# FluxR3-v2.net
KiCad netlist of a schematic drawn in EAGLE
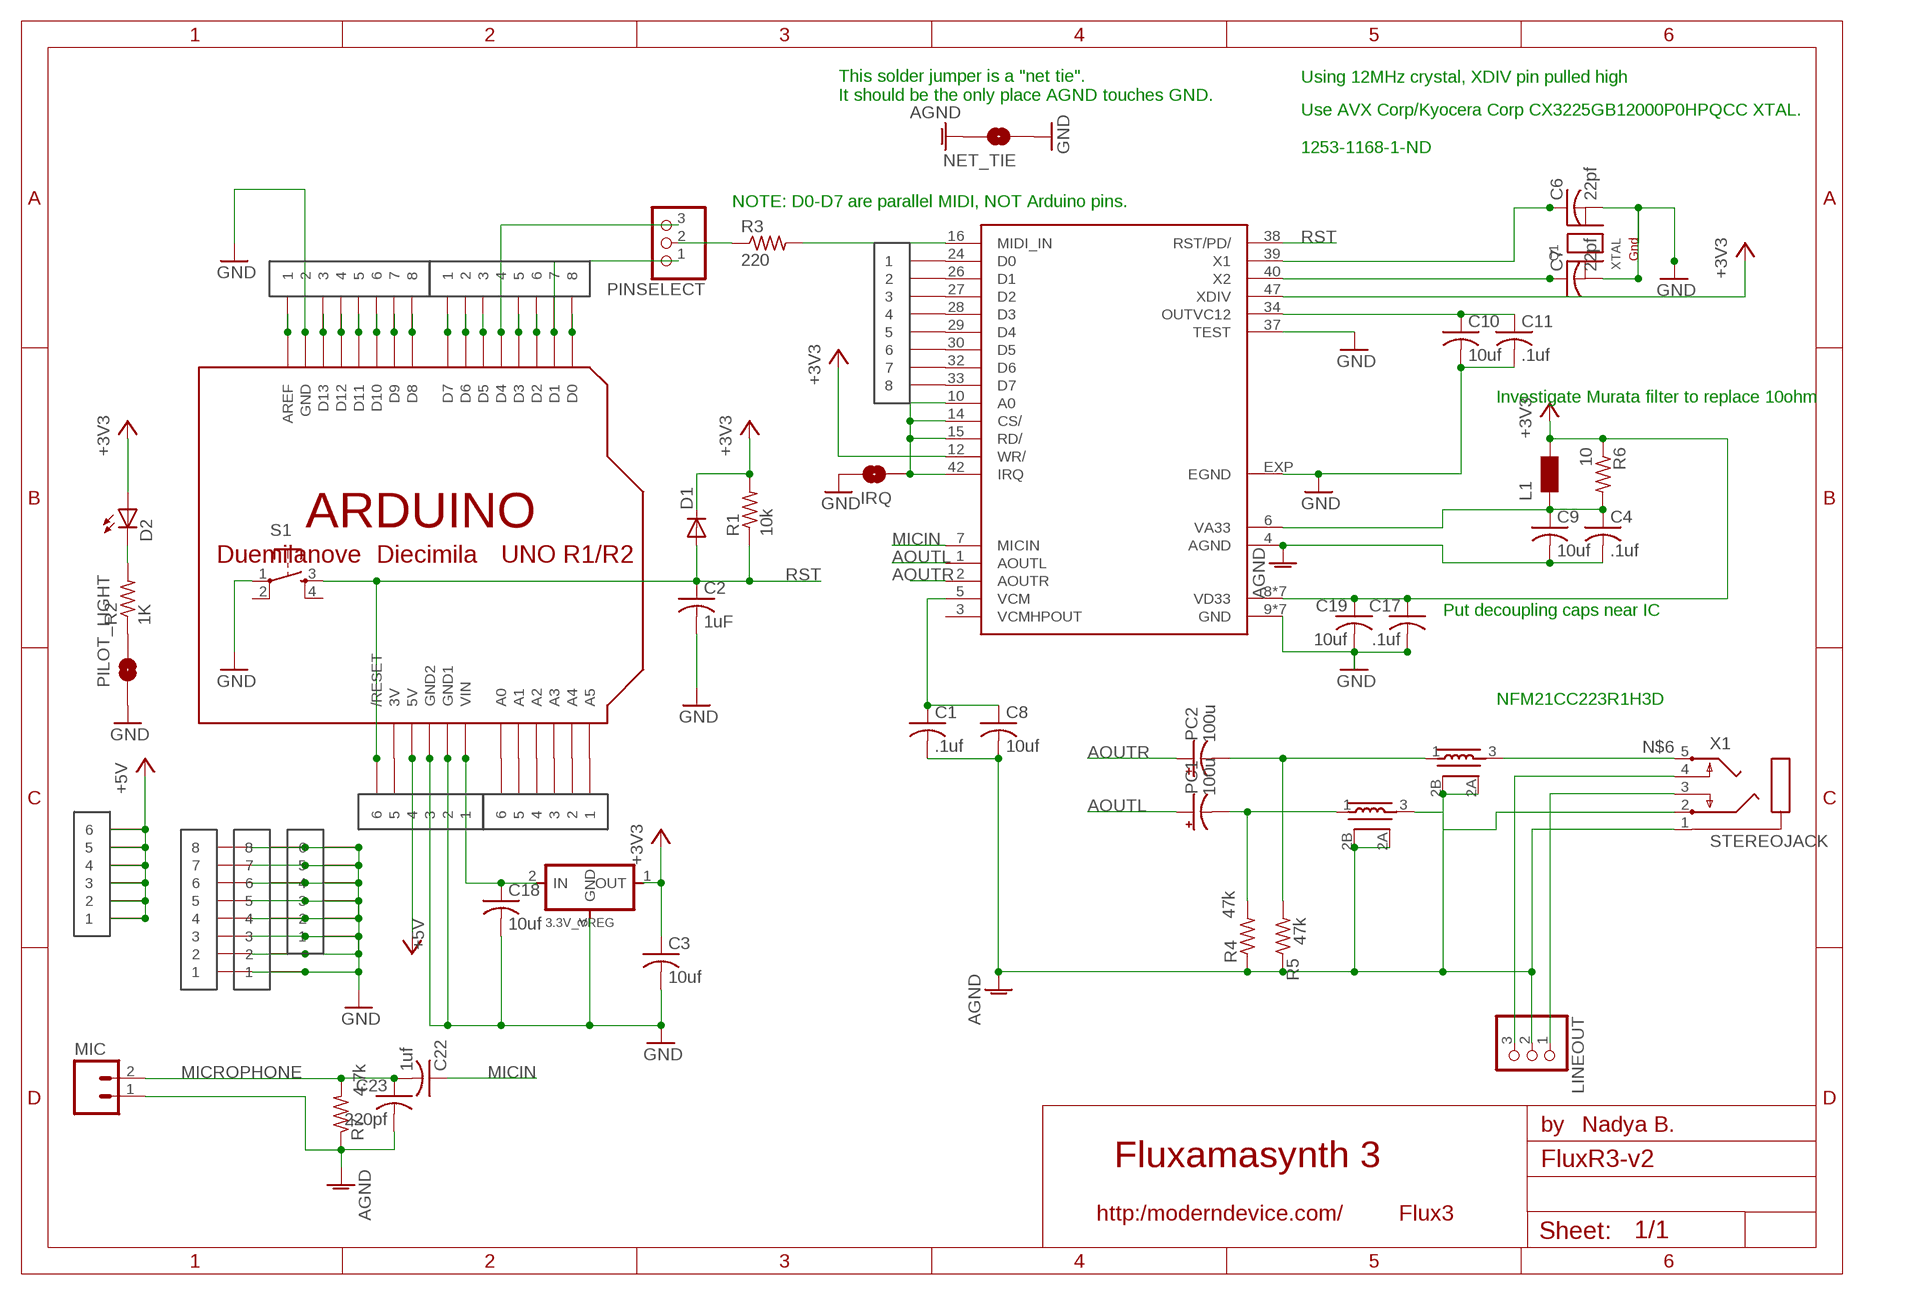
[diagram p0: schematic, sheet 1]

(export (version "E")
  (design (tool "Eeschema 10.0.6"))
  (components
    (comp (ref "3.3V_VREG")
      (value "REGULATORSOT23")
      (footprint "eagle-import:SOT23")
      (libsource (lib "eagle-import") (part "REGULATORSOT23"))
    )
    (comp (ref "ARDUINO")
      (value "ARDUINO-NOHOLE")
      (footprint "eagle-import:ARDUINO-NOHOLE")
      (libsource (lib "eagle-import") (part "ARDUINO-NOHOLE"))
    )
    (comp (ref "C1")
      (value ".1uf")
      (footprint "eagle-import:C0603K")
      (libsource (lib "eagle-import") (part "C-USC0603K"))
    )
    (comp (ref "C2")
      (value "1uF")
      (footprint "eagle-import:C0805")
      (libsource (lib "eagle-import") (part "C-USC0805"))
    )
    (comp (ref "C3")
      (value "10uf")
      (footprint "eagle-import:C0805")
      (libsource (lib "eagle-import") (part "C-USC0805"))
    )
    (comp (ref "C4")
      (value ".1uf")
      (footprint "eagle-import:C0603K")
      (libsource (lib "eagle-import") (part "C-USC0603K"))
    )
    (comp (ref "C6")
      (value "22pf")
      (footprint "eagle-import:C0805")
      (libsource (lib "eagle-import") (part "C-USC0805"))
    )
    (comp (ref "C7")
      (value "22pf")
      (footprint "eagle-import:C0805")
      (libsource (lib "eagle-import") (part "C-USC0805"))
    )
    (comp (ref "C8")
      (value "10uf")
      (footprint "eagle-import:C0805")
      (libsource (lib "eagle-import") (part "C-USC0805"))
    )
    (comp (ref "C9")
      (value "10uf")
      (footprint "eagle-import:C0805")
      (libsource (lib "eagle-import") (part "C-USC0805"))
    )
    (comp (ref "C10")
      (value "10uf")
      (footprint "eagle-import:C0805")
      (libsource (lib "eagle-import") (part "C-USC0805"))
    )
    (comp (ref "C11")
      (value ".1uf")
      (footprint "eagle-import:C0603K")
      (libsource (lib "eagle-import") (part "C-USC0603K"))
    )
    (comp (ref "C17")
      (value ".1uf")
      (footprint "eagle-import:C0603K")
      (libsource (lib "eagle-import") (part "C-USC0603K"))
    )
    (comp (ref "C18")
      (value "10uf")
      (footprint "eagle-import:C0805")
      (libsource (lib "eagle-import") (part "C-USC0805"))
    )
    (comp (ref "C19")
      (value "10uf")
      (footprint "eagle-import:C0805")
      (libsource (lib "eagle-import") (part "C-USC0805"))
    )
    (comp (ref "C22")
      (value "1uf")
      (footprint "eagle-import:C0805")
      (libsource (lib "eagle-import") (part "C-USC0805"))
    )
    (comp (ref "C23")
      (value "220pf")
      (footprint "eagle-import:C0805")
      (libsource (lib "eagle-import") (part "C-USC0805"))
    )
    (comp (ref "D1")
      (value "DIODESOD123")
      (footprint "eagle-import:SOD123")
      (libsource (lib "eagle-import") (part "DIODESOD123"))
    )
    (comp (ref "D2")
      (value "LED1206")
      (footprint "eagle-import:LED-1206")
      (libsource (lib "eagle-import") (part "LED1206"))
    )
    (comp (ref "IRQ")
      (value "MODERNDEVICE_SOLDERJUMPERTRACE")
      (footprint "eagle-import:MODERNDEVICE_SJ_2S-TRACE")
      (libsource (lib "eagle-import") (part "MODERNDEVICE_SOLDERJUMPERTRACE"))
    )
    (comp (ref "L1")
      (value "FERRITE_BEAD_L0603")
      (footprint "eagle-import:R0603")
      (libsource (lib "eagle-import") (part "FERRITE_BEAD_L0603"))
    )
    (comp (ref "LINEOUT")
      (value "PINHD-1X3")
      (footprint "eagle-import:1X03")
      (libsource (lib "eagle-import") (part "PINHD-1X3"))
    )
    (comp (ref "MIC")
      (value "M02PTH")
      (footprint "eagle-import:1X02")
      (libsource (lib "eagle-import") (part "M02PTH"))
    )
    (comp (ref "MIDI")
      (value "1X8_CLEAN")
      (footprint "eagle-import:1X8_CLEAN")
      (libsource (lib "eagle-import") (part "1X8_CLEAN"))
    )
    (comp (ref "NET_TIE")
      (value "MODERNDEVICE_SOLDERJUMPERTRACE")
      (footprint "eagle-import:MODERNDEVICE_SJ_2S-TRACE")
      (libsource (lib "eagle-import") (part "MODERNDEVICE_SOLDERJUMPERTRACE"))
    )
    (comp (ref "PC1")
      (value "100u")
      (footprint "eagle-import:PANASONIC_E")
      (libsource (lib "eagle-import") (part "CPOL-USE"))
    )
    (comp (ref "PC2")
      (value "100u")
      (footprint "eagle-import:PANASONIC_E")
      (libsource (lib "eagle-import") (part "CPOL-USE"))
    )
    (comp (ref "PILOT_LIGHT")
      (value "MODERNDEVICE_SOLDERJUMPERTRACE")
      (footprint "eagle-import:MODERNDEVICE_SJ_2S-TRACE")
      (libsource (lib "eagle-import") (part "MODERNDEVICE_SOLDERJUMPERTRACE"))
    )
    (comp (ref "PINSELECT")
      (value "PINHD-1X3")
      (footprint "eagle-import:1X03")
      (libsource (lib "eagle-import") (part "PINHD-1X3"))
    )
    (comp (ref "Q1")
      (value "XTAL")
      (footprint "eagle-import:MODERNDEVICE_NX3225")
      (libsource (lib "eagle-import") (part "MODERNDEVICE_XTAL-4-3225"))
    )
    (comp (ref "R1")
      (value "10k")
      (footprint "eagle-import:M0805")
      (libsource (lib "eagle-import") (part "R-US_M0805"))
    )
    (comp (ref "R2")
      (value "1K")
      (footprint "eagle-import:M0805")
      (libsource (lib "eagle-import") (part "R-US_M0805"))
    )
    (comp (ref "R3")
      (value "220")
      (footprint "eagle-import:M0805")
      (libsource (lib "eagle-import") (part "R-US_M0805"))
    )
    (comp (ref "R4")
      (value "47k")
      (footprint "eagle-import:R0603")
      (libsource (lib "eagle-import") (part "R-US_R0603"))
    )
    (comp (ref "R5")
      (value "47k")
      (footprint "eagle-import:R0603")
      (libsource (lib "eagle-import") (part "R-US_R0603"))
    )
    (comp (ref "R6")
      (value "10")
      (footprint "eagle-import:M0805")
      (libsource (lib "eagle-import") (part "R-US_M0805"))
    )
    (comp (ref "R7")
      (value "4.7k")
      (footprint "eagle-import:M0805")
      (libsource (lib "eagle-import") (part "R-US_M0805"))
    )
    (comp (ref "S1")
      (value "6MM_SWITCH6MM_SWITCH")
      (footprint "eagle-import:6MM_SWITCH")
      (libsource (lib "eagle-import") (part "6MM_SWITCH6MM_SWITCH"))
    )
    (comp (ref "SAM2695")
      (value "SAM2695")
      (footprint "eagle-import:QFN48")
      (libsource (lib "eagle-import") (part "SAM2695"))
    )
    (comp (ref "U$1")
      (value "1X8_CLEAN")
      (footprint "eagle-import:1X8_CLEAN")
      (libsource (lib "eagle-import") (part "1X8_CLEAN"))
    )
    (comp (ref "U$2")
      (value "1X6_CLEAN")
      (footprint "eagle-import:1X6_CLEAN")
      (libsource (lib "eagle-import") (part "1X6_CLEAN"))
    )
    (comp (ref "U$3")
      (value "1X6_CLEAN")
      (footprint "eagle-import:1X6_CLEAN")
      (libsource (lib "eagle-import") (part "1X6_CLEAN"))
    )
    (comp (ref "U$4")
      (value "NFM21CC223R1H3D")
      (footprint "eagle-import:3PC")
      (libsource (lib "eagle-import") (part "NFM21CC223R1H3D"))
    )
    (comp (ref "U$5")
      (value "NFM21CC223R1H3D")
      (footprint "eagle-import:3PC")
      (libsource (lib "eagle-import") (part "NFM21CC223R1H3D"))
    )
    (comp (ref "U$6")
      (value "1X6_CLEAN")
      (footprint "eagle-import:1X6_CLEAN")
      (libsource (lib "eagle-import") (part "1X6_CLEAN"))
    )
    (comp (ref "U$8")
      (value "1X6_CLEAN")
      (footprint "eagle-import:1X6_CLEAN")
      (libsource (lib "eagle-import") (part "1X6_CLEAN"))
    )
    (comp (ref "U$9")
      (value "1X8_CLEAN")
      (footprint "eagle-import:1X8_CLEAN")
      (libsource (lib "eagle-import") (part "1X8_CLEAN"))
    )
    (comp (ref "U$11")
      (value "1X8_CLEAN")
      (footprint "eagle-import:1X8_CLEAN")
      (libsource (lib "eagle-import") (part "1X8_CLEAN"))
    )
    (comp (ref "U$13")
      (value "1X8_CLEAN")
      (footprint "eagle-import:1X8_CLEAN")
      (libsource (lib "eagle-import") (part "1X8_CLEAN"))
    )
    (comp (ref "X1")
      (value "STEREOJACK")
      (footprint "eagle-import:STX3100")
      (libsource (lib "eagle-import") (part "STEREOJACK"))
    )
  )
  (nets
    (net (code "1") (name "+3V3") (class "Default")
      (node (ref "3.3V_VREG") (pin "1") (pinfunction "OUT_1") (pintype "bidirectional"))
      (node (ref "C17") (pin "1") (pinfunction "1_1") (pintype "passive"))
      (node (ref "C19") (pin "1") (pinfunction "1_1") (pintype "passive"))
      (node (ref "C3") (pin "1") (pinfunction "1_1") (pintype "passive"))
      (node (ref "D1") (pin "CATHODE") (pinfunction "C_CATHODE") (pintype "passive"))
      (node (ref "D2") (pin "A") (pinfunction "A_A") (pintype "passive"))
      (node (ref "L1") (pin "2") (pinfunction "2_2") (pintype "passive"))
      (node (ref "R1") (pin "2") (pinfunction "2_2") (pintype "passive"))
      (node (ref "R6") (pin "1") (pinfunction "1_1") (pintype "passive"))
      (node (ref "SAM2695") (pin "11") (pinfunction "VD33_11") (pintype "power_in"))
      (node (ref "SAM2695") (pin "12") (pinfunction "WR/_12") (pintype "input"))
      (node (ref "SAM2695") (pin "20") (pinfunction "VD33_20") (pintype "power_in"))
      (node (ref "SAM2695") (pin "31") (pinfunction "VD33_31") (pintype "power_in"))
      (node (ref "SAM2695") (pin "35") (pinfunction "VD33_35") (pintype "power_in"))
      (node (ref "SAM2695") (pin "41") (pinfunction "VD33_41") (pintype "power_in"))
      (node (ref "SAM2695") (pin "46") (pinfunction "VD33_46") (pintype "power_in"))
      (node (ref "SAM2695") (pin "47") (pinfunction "XDIV_47") (pintype "input"))
      (node (ref "SAM2695") (pin "8") (pinfunction "VD33_8") (pintype "power_in"))
    )
    (net (code "2") (name "+5V") (class "Default")
      (node (ref "ARDUINO") (pin "5V") (pinfunction "5V_5V") (pintype "power_in"))
      (node (ref "U$2") (pin "P$1") (pinfunction "1_P$1") (pintype "bidirectional"))
      (node (ref "U$2") (pin "P$2") (pinfunction "2_P$2") (pintype "bidirectional"))
      (node (ref "U$2") (pin "P$3") (pinfunction "3_P$3") (pintype "bidirectional"))
      (node (ref "U$2") (pin "P$4") (pinfunction "4_P$4") (pintype "bidirectional"))
      (node (ref "U$2") (pin "P$5") (pinfunction "5_P$5") (pintype "bidirectional"))
      (node (ref "U$2") (pin "P$6") (pinfunction "6_P$6") (pintype "bidirectional"))
      (node (ref "U$6") (pin "P$4") (pinfunction "4_P$4") (pintype "bidirectional"))
    )
    (net (code "3") (name "/AOUTL") (class "Default")
      (node (ref "PC1") (pin "+") (pinfunction "+_+") (pintype "passive"))
      (node (ref "SAM2695") (pin "1") (pinfunction "AOUTL_1") (pintype "output"))
    )
    (net (code "4") (name "/AOUTR") (class "Default")
      (node (ref "PC2") (pin "+") (pinfunction "+_+") (pintype "passive"))
      (node (ref "SAM2695") (pin "2") (pinfunction "AOUTR_2") (pintype "output"))
    )
    (net (code "5") (name "/MICIN") (class "Default")
      (node (ref "C22") (pin "1") (pinfunction "1_1") (pintype "passive"))
      (node (ref "SAM2695") (pin "7") (pinfunction "MICIN_7") (pintype "input"))
    )
    (net (code "6") (name "/MICROPHONE") (class "Default")
      (node (ref "C22") (pin "2") (pinfunction "2_2") (pintype "passive"))
      (node (ref "C23") (pin "1") (pinfunction "1_1") (pintype "passive"))
      (node (ref "MIC") (pin "2") (pinfunction "2_2") (pintype "passive"))
      (node (ref "R7") (pin "2") (pinfunction "2_2") (pintype "passive"))
    )
    (net (code "7") (name "/N$6") (class "Default")
      (node (ref "U$4") (pin "3") (pinfunction "3_3") (pintype "bidirectional"))
      (node (ref "X1") (pin "5") (pinfunction "5_5") (pintype "passive"))
    )
    (net (code "8") (name "/RST") (class "Default")
      (node (ref "ARDUINO") (pin "RESET") (pinfunction "/RESET_RESET") (pintype "bidirectional"))
      (node (ref "C2") (pin "1") (pinfunction "1_1") (pintype "passive"))
      (node (ref "D1") (pin "ANODE") (pinfunction "A_ANODE") (pintype "passive"))
      (node (ref "R1") (pin "1") (pinfunction "1_1") (pintype "passive"))
      (node (ref "S1") (pin "3") (pinfunction "S_3") (pintype "passive"))
      (node (ref "SAM2695") (pin "38") (pinfunction "RST/PD/_38") (pintype "input"))
      (node (ref "U$6") (pin "P$6") (pinfunction "6_P$6") (pintype "bidirectional"))
    )
    (net (code "9") (name "AGND") (class "Default")
      (node (ref "C1") (pin "2") (pinfunction "2_2") (pintype "passive"))
      (node (ref "C23") (pin "2") (pinfunction "2_2") (pintype "passive"))
      (node (ref "C4") (pin "2") (pinfunction "2_2") (pintype "passive"))
      (node (ref "C8") (pin "2") (pinfunction "2_2") (pintype "passive"))
      (node (ref "C9") (pin "2") (pinfunction "2_2") (pintype "passive"))
      (node (ref "LINEOUT") (pin "2") (pinfunction "2_2") (pintype "passive"))
      (node (ref "MIC") (pin "1") (pinfunction "1_1") (pintype "passive"))
      (node (ref "NET_TIE") (pin "2") (pinfunction "2_2") (pintype "passive"))
      (node (ref "R4") (pin "1") (pinfunction "1_1") (pintype "passive"))
      (node (ref "R5") (pin "1") (pinfunction "1_1") (pintype "passive"))
      (node (ref "R7") (pin "1") (pinfunction "1_1") (pintype "passive"))
      (node (ref "SAM2695") (pin "4") (pinfunction "AGND_4") (pintype "power_in"))
      (node (ref "U$4") (pin "2A") (pinfunction "2A_2A") (pintype "power_in"))
      (node (ref "U$4") (pin "2B") (pinfunction "2B_2B") (pintype "power_in"))
      (node (ref "U$5") (pin "2A") (pinfunction "2A_2A") (pintype "power_in"))
      (node (ref "U$5") (pin "2B") (pinfunction "2B_2B") (pintype "power_in"))
      (node (ref "X1") (pin "1") (pinfunction "1_1") (pintype "passive"))
    )
    (net (code "10") (name "GND") (class "Default")
      (node (ref "3.3V_VREG") (pin "3") (pinfunction "GND_3") (pintype "bidirectional"))
      (node (ref "ARDUINO") (pin "GND") (pinfunction "GND_GND") (pintype "power_in"))
      (node (ref "ARDUINO") (pin "GND1") (pinfunction "GND1_GND1") (pintype "power_in"))
      (node (ref "ARDUINO") (pin "GND2") (pinfunction "GND2_GND2") (pintype "power_in"))
      (node (ref "C10") (pin "2") (pinfunction "2_2") (pintype "passive"))
      (node (ref "C11") (pin "2") (pinfunction "2_2") (pintype "passive"))
      (node (ref "C17") (pin "2") (pinfunction "2_2") (pintype "passive"))
      (node (ref "C18") (pin "2") (pinfunction "2_2") (pintype "passive"))
      (node (ref "C19") (pin "2") (pinfunction "2_2") (pintype "passive"))
      (node (ref "C2") (pin "2") (pinfunction "2_2") (pintype "passive"))
      (node (ref "C3") (pin "2") (pinfunction "2_2") (pintype "passive"))
      (node (ref "C6") (pin "2") (pinfunction "2_2") (pintype "passive"))
      (node (ref "C7") (pin "2") (pinfunction "2_2") (pintype "passive"))
      (node (ref "IRQ") (pin "2") (pinfunction "2_2") (pintype "passive"))
      (node (ref "NET_TIE") (pin "1") (pinfunction "1_1") (pintype "passive"))
      (node (ref "PILOT_LIGHT") (pin "1") (pinfunction "1_1") (pintype "passive"))
      (node (ref "Q1") (pin "2") (pinfunction "G2_2") (pintype "power_in"))
      (node (ref "Q1") (pin "4") (pinfunction "G1_4") (pintype "power_in"))
      (node (ref "S1") (pin "1") (pinfunction "P_1") (pintype "passive"))
      (node (ref "SAM2695") (pin "13") (pinfunction "GND_13") (pintype "power_in"))
      (node (ref "SAM2695") (pin "18") (pinfunction "GND_18") (pintype "power_in"))
      (node (ref "SAM2695") (pin "25") (pinfunction "GND_25") (pintype "power_in"))
      (node (ref "SAM2695") (pin "36") (pinfunction "GND_36") (pintype "power_in"))
      (node (ref "SAM2695") (pin "37") (pinfunction "TEST_37") (pintype "input"))
      (node (ref "SAM2695") (pin "45") (pinfunction "GND_45") (pintype "power_in"))
      (node (ref "SAM2695") (pin "48") (pinfunction "GND_48") (pintype "power_in"))
      (node (ref "SAM2695") (pin "9") (pinfunction "GND_9") (pintype "power_in"))
      (node (ref "SAM2695") (pin "EXP") (pinfunction "EGND_EXP") (pintype "power_in"))
      (node (ref "U$1") (pin "P$1") (pinfunction "1_P$1") (pintype "bidirectional"))
      (node (ref "U$1") (pin "P$2") (pinfunction "2_P$2") (pintype "bidirectional"))
      (node (ref "U$1") (pin "P$3") (pinfunction "3_P$3") (pintype "bidirectional"))
      (node (ref "U$1") (pin "P$4") (pinfunction "4_P$4") (pintype "bidirectional"))
      (node (ref "U$1") (pin "P$5") (pinfunction "5_P$5") (pintype "bidirectional"))
      (node (ref "U$1") (pin "P$6") (pinfunction "6_P$6") (pintype "bidirectional"))
      (node (ref "U$1") (pin "P$7") (pinfunction "7_P$7") (pintype "bidirectional"))
      (node (ref "U$1") (pin "P$8") (pinfunction "8_P$8") (pintype "bidirectional"))
      (node (ref "U$11") (pin "P$1") (pinfunction "1_P$1") (pintype "bidirectional"))
      (node (ref "U$11") (pin "P$2") (pinfunction "2_P$2") (pintype "bidirectional"))
      (node (ref "U$11") (pin "P$3") (pinfunction "3_P$3") (pintype "bidirectional"))
      (node (ref "U$11") (pin "P$4") (pinfunction "4_P$4") (pintype "bidirectional"))
      (node (ref "U$11") (pin "P$5") (pinfunction "5_P$5") (pintype "bidirectional"))
      (node (ref "U$11") (pin "P$6") (pinfunction "6_P$6") (pintype "bidirectional"))
      (node (ref "U$11") (pin "P$7") (pinfunction "7_P$7") (pintype "bidirectional"))
      (node (ref "U$11") (pin "P$8") (pinfunction "8_P$8") (pintype "bidirectional"))
      (node (ref "U$13") (pin "P$2") (pinfunction "2_P$2") (pintype "bidirectional"))
      (node (ref "U$3") (pin "P$1") (pinfunction "1_P$1") (pintype "bidirectional"))
      (node (ref "U$3") (pin "P$2") (pinfunction "2_P$2") (pintype "bidirectional"))
      (node (ref "U$3") (pin "P$3") (pinfunction "3_P$3") (pintype "bidirectional"))
      (node (ref "U$3") (pin "P$4") (pinfunction "4_P$4") (pintype "bidirectional"))
      (node (ref "U$3") (pin "P$5") (pinfunction "5_P$5") (pintype "bidirectional"))
      (node (ref "U$3") (pin "P$6") (pinfunction "6_P$6") (pintype "bidirectional"))
      (node (ref "U$6") (pin "P$2") (pinfunction "2_P$2") (pintype "bidirectional"))
      (node (ref "U$6") (pin "P$3") (pinfunction "3_P$3") (pintype "bidirectional"))
    )
    (net (code "11") (name "Net-(3.3V_VREG-IN)") (class "Default")
      (node (ref "3.3V_VREG") (pin "2") (pinfunction "IN_2") (pintype "bidirectional"))
      (node (ref "ARDUINO") (pin "VIN") (pinfunction "VIN_VIN") (pintype "power_in"))
      (node (ref "C18") (pin "1") (pinfunction "1_1") (pintype "passive"))
      (node (ref "U$6") (pin "P$1") (pinfunction "1_P$1") (pintype "bidirectional"))
    )
    (net (code "12") (name "Net-(D2-PadC)") (class "Default")
      (node (ref "D2") (pin "C") (pinfunction "C_C") (pintype "passive"))
      (node (ref "R2") (pin "2") (pinfunction "2_2") (pintype "passive"))
    )
    (net (code "13") (name "Net-(LINEOUT-Pad1)") (class "Default")
      (node (ref "LINEOUT") (pin "1") (pinfunction "1_1") (pintype "passive"))
      (node (ref "X1") (pin "3") (pinfunction "3_3") (pintype "passive"))
    )
    (net (code "14") (name "Net-(LINEOUT-Pad3)") (class "Default")
      (node (ref "LINEOUT") (pin "3") (pinfunction "3_3") (pintype "passive"))
      (node (ref "X1") (pin "4") (pinfunction "4_4") (pintype "passive"))
    )
    (net (code "15") (name "Net-(MIDI-1)") (class "Default")
      (node (ref "MIDI") (pin "P$1") (pinfunction "1_P$1") (pintype "bidirectional"))
      (node (ref "SAM2695") (pin "24") (pinfunction "D0_24") (pintype "bidirectional"))
    )
    (net (code "16") (name "Net-(MIDI-2)") (class "Default")
      (node (ref "MIDI") (pin "P$2") (pinfunction "2_P$2") (pintype "bidirectional"))
      (node (ref "SAM2695") (pin "26") (pinfunction "D1_26") (pintype "bidirectional"))
    )
    (net (code "17") (name "Net-(MIDI-3)") (class "Default")
      (node (ref "MIDI") (pin "P$3") (pinfunction "3_P$3") (pintype "bidirectional"))
      (node (ref "SAM2695") (pin "27") (pinfunction "D2_27") (pintype "bidirectional"))
    )
    (net (code "18") (name "Net-(MIDI-4)") (class "Default")
      (node (ref "MIDI") (pin "P$4") (pinfunction "4_P$4") (pintype "bidirectional"))
      (node (ref "SAM2695") (pin "28") (pinfunction "D3_28") (pintype "bidirectional"))
    )
    (net (code "19") (name "Net-(MIDI-5)") (class "Default")
      (node (ref "MIDI") (pin "P$5") (pinfunction "5_P$5") (pintype "bidirectional"))
      (node (ref "SAM2695") (pin "29") (pinfunction "D4_29") (pintype "bidirectional"))
    )
    (net (code "20") (name "Net-(MIDI-6)") (class "Default")
      (node (ref "MIDI") (pin "P$6") (pinfunction "6_P$6") (pintype "bidirectional"))
      (node (ref "SAM2695") (pin "30") (pinfunction "D5_30") (pintype "bidirectional"))
    )
    (net (code "21") (name "Net-(MIDI-7)") (class "Default")
      (node (ref "MIDI") (pin "P$7") (pinfunction "7_P$7") (pintype "bidirectional"))
      (node (ref "SAM2695") (pin "32") (pinfunction "D6_32") (pintype "bidirectional"))
    )
    (net (code "22") (name "Net-(MIDI-8)") (class "Default")
      (node (ref "MIDI") (pin "P$8") (pinfunction "8_P$8") (pintype "bidirectional"))
      (node (ref "SAM2695") (pin "33") (pinfunction "D7_33") (pintype "bidirectional"))
    )
    (net (code "23") (name "Net-(PC1-Pad-)") (class "Default")
      (node (ref "PC1") (pin "-") (pinfunction "-_-") (pintype "passive"))
      (node (ref "R4") (pin "2") (pinfunction "2_2") (pintype "passive"))
      (node (ref "U$5") (pin "1") (pinfunction "1_1") (pintype "bidirectional"))
    )
    (net (code "24") (name "Net-(PC2-Pad-)") (class "Default")
      (node (ref "PC2") (pin "-") (pinfunction "-_-") (pintype "passive"))
      (node (ref "R5") (pin "2") (pinfunction "2_2") (pintype "passive"))
      (node (ref "U$4") (pin "1") (pinfunction "1_1") (pintype "bidirectional"))
    )
    (net (code "25") (name "Net-(PILOT_LIGHT-Pad2)") (class "Default")
      (node (ref "PILOT_LIGHT") (pin "2") (pinfunction "2_2") (pintype "passive"))
      (node (ref "R2") (pin "1") (pinfunction "1_1") (pintype "passive"))
    )
    (net (code "26") (name "Net-(PINSELECT-Pad2)") (class "Default")
      (node (ref "PINSELECT") (pin "2") (pinfunction "2_2") (pintype "passive"))
      (node (ref "R3") (pin "1") (pinfunction "1_1") (pintype "passive"))
    )
    (net (code "27") (name "Net-(SAM2695-A0)") (class "Default")
      (node (ref "IRQ") (pin "1") (pinfunction "1_1") (pintype "passive"))
      (node (ref "SAM2695") (pin "10") (pinfunction "A0_10") (pintype "input"))
      (node (ref "SAM2695") (pin "14") (pinfunction "CS/_14") (pintype "input"))
      (node (ref "SAM2695") (pin "15") (pinfunction "RD/_15") (pintype "input"))
      (node (ref "SAM2695") (pin "42") (pinfunction "IRQ_42") (pintype "output"))
    )
    (net (code "28") (name "Net-(SAM2695-MIDI_IN)") (class "Default")
      (node (ref "R3") (pin "2") (pinfunction "2_2") (pintype "passive"))
      (node (ref "SAM2695") (pin "16") (pinfunction "MIDI_IN_16") (pintype "input"))
    )
    (net (code "29") (name "Net-(SAM2695-OUTVC12)") (class "Default")
      (node (ref "C10") (pin "1") (pinfunction "1_1") (pintype "passive"))
      (node (ref "C11") (pin "1") (pinfunction "1_1") (pintype "passive"))
      (node (ref "SAM2695") (pin "34") (pinfunction "OUTVC12_34") (pintype "power_in"))
    )
    (net (code "30") (name "Net-(SAM2695-VA33)") (class "Default")
      (node (ref "C4") (pin "1") (pinfunction "1_1") (pintype "passive"))
      (node (ref "C9") (pin "1") (pinfunction "1_1") (pintype "passive"))
      (node (ref "L1") (pin "1") (pinfunction "1_1") (pintype "passive"))
      (node (ref "R6") (pin "2") (pinfunction "2_2") (pintype "passive"))
      (node (ref "SAM2695") (pin "6") (pinfunction "VA33_6") (pintype "power_in"))
    )
    (net (code "31") (name "Net-(SAM2695-VCM)") (class "Default")
      (node (ref "C1") (pin "1") (pinfunction "1_1") (pintype "passive"))
      (node (ref "C8") (pin "1") (pinfunction "1_1") (pintype "passive"))
      (node (ref "SAM2695") (pin "5") (pinfunction "VCM_5") (pintype "output"))
    )
    (net (code "32") (name "Net-(SAM2695-X1)") (class "Default")
      (node (ref "C6") (pin "1") (pinfunction "1_1") (pintype "passive"))
      (node (ref "SAM2695") (pin "39") (pinfunction "X1_39") (pintype "bidirectional"))
    )
    (net (code "33") (name "Net-(SAM2695-X2)") (class "Default")
      (node (ref "C7") (pin "1") (pinfunction "1_1") (pintype "passive"))
      (node (ref "SAM2695") (pin "40") (pinfunction "X2_40") (pintype "bidirectional"))
    )
    (net (code "34") (name "Net-(U$5-Pad3)") (class "Default")
      (node (ref "U$5") (pin "3") (pinfunction "3_3") (pintype "bidirectional"))
      (node (ref "X1") (pin "2") (pinfunction "2_2") (pintype "passive"))
    )
    (net (code "35") (name "Net-(U$6-5)") (class "Default")
      (node (ref "ARDUINO") (pin "3V") (pinfunction "3V_3V") (pintype "power_in"))
      (node (ref "U$6") (pin "P$5") (pinfunction "5_P$5") (pintype "bidirectional"))
    )
    (net (code "36") (name "Net-(U$8-1)") (class "Default")
      (node (ref "ARDUINO") (pin "A5") (pinfunction "A5_A5") (pintype "bidirectional"))
      (node (ref "U$8") (pin "P$1") (pinfunction "1_P$1") (pintype "bidirectional"))
    )
    (net (code "37") (name "Net-(U$8-2)") (class "Default")
      (node (ref "ARDUINO") (pin "A4") (pinfunction "A4_A4") (pintype "bidirectional"))
      (node (ref "U$8") (pin "P$2") (pinfunction "2_P$2") (pintype "bidirectional"))
    )
    (net (code "38") (name "Net-(U$8-3)") (class "Default")
      (node (ref "ARDUINO") (pin "A3") (pinfunction "A3_A3") (pintype "bidirectional"))
      (node (ref "U$8") (pin "P$3") (pinfunction "3_P$3") (pintype "bidirectional"))
    )
    (net (code "39") (name "Net-(U$8-4)") (class "Default")
      (node (ref "ARDUINO") (pin "A2") (pinfunction "A2_A2") (pintype "bidirectional"))
      (node (ref "U$8") (pin "P$4") (pinfunction "4_P$4") (pintype "bidirectional"))
    )
    (net (code "40") (name "Net-(U$8-5)") (class "Default")
      (node (ref "ARDUINO") (pin "A1") (pinfunction "A1_A1") (pintype "bidirectional"))
      (node (ref "U$8") (pin "P$5") (pinfunction "5_P$5") (pintype "bidirectional"))
    )
    (net (code "41") (name "Net-(U$8-6)") (class "Default")
      (node (ref "ARDUINO") (pin "A0") (pinfunction "A0_A0") (pintype "bidirectional"))
      (node (ref "U$8") (pin "P$6") (pinfunction "6_P$6") (pintype "bidirectional"))
    )
    (net (code "42") (name "Net-(U$9-1)") (class "Default")
      (node (ref "ARDUINO") (pin "D7") (pinfunction "D7_D7") (pintype "bidirectional"))
      (node (ref "U$9") (pin "P$1") (pinfunction "1_P$1") (pintype "bidirectional"))
    )
    (net (code "43") (name "Net-(U$9-2)") (class "Default")
      (node (ref "ARDUINO") (pin "D6") (pinfunction "D6_D6") (pintype "bidirectional"))
      (node (ref "U$9") (pin "P$2") (pinfunction "2_P$2") (pintype "bidirectional"))
    )
    (net (code "44") (name "Net-(U$9-3)") (class "Default")
      (node (ref "ARDUINO") (pin "D5") (pinfunction "D5_D5") (pintype "bidirectional"))
      (node (ref "U$9") (pin "P$3") (pinfunction "3_P$3") (pintype "bidirectional"))
    )
    (net (code "45") (name "Net-(U$9-4)") (class "Default")
      (node (ref "ARDUINO") (pin "D4") (pinfunction "D4_D4") (pintype "bidirectional"))
      (node (ref "PINSELECT") (pin "3") (pinfunction "3_3") (pintype "passive"))
      (node (ref "U$9") (pin "P$4") (pinfunction "4_P$4") (pintype "bidirectional"))
    )
    (net (code "46") (name "Net-(U$9-5)") (class "Default")
      (node (ref "ARDUINO") (pin "D3") (pinfunction "D3_D3") (pintype "bidirectional"))
      (node (ref "U$9") (pin "P$5") (pinfunction "5_P$5") (pintype "bidirectional"))
    )
    (net (code "47") (name "Net-(U$9-6)") (class "Default")
      (node (ref "ARDUINO") (pin "D2") (pinfunction "D2_D2") (pintype "bidirectional"))
      (node (ref "U$9") (pin "P$6") (pinfunction "6_P$6") (pintype "bidirectional"))
    )
    (net (code "48") (name "Net-(U$9-7)") (class "Default")
      (node (ref "ARDUINO") (pin "D1") (pinfunction "D1_D1") (pintype "bidirectional"))
      (node (ref "PINSELECT") (pin "1") (pinfunction "1_1") (pintype "passive"))
      (node (ref "U$9") (pin "P$7") (pinfunction "7_P$7") (pintype "bidirectional"))
    )
    (net (code "49") (name "Net-(U$9-8)") (class "Default")
      (node (ref "ARDUINO") (pin "D0") (pinfunction "D0_D0") (pintype "bidirectional"))
      (node (ref "U$9") (pin "P$8") (pinfunction "8_P$8") (pintype "bidirectional"))
    )
    (net (code "50") (name "Net-(U$13-1)") (class "Default")
      (node (ref "ARDUINO") (pin "AREF") (pinfunction "AREF_AREF") (pintype "bidirectional"))
      (node (ref "U$13") (pin "P$1") (pinfunction "1_P$1") (pintype "bidirectional"))
    )
    (net (code "51") (name "Net-(U$13-3)") (class "Default")
      (node (ref "ARDUINO") (pin "D13") (pinfunction "D13_D13") (pintype "bidirectional"))
      (node (ref "U$13") (pin "P$3") (pinfunction "3_P$3") (pintype "bidirectional"))
    )
    (net (code "52") (name "Net-(U$13-4)") (class "Default")
      (node (ref "ARDUINO") (pin "D12") (pinfunction "D12_D12") (pintype "bidirectional"))
      (node (ref "U$13") (pin "P$4") (pinfunction "4_P$4") (pintype "bidirectional"))
    )
    (net (code "53") (name "Net-(U$13-5)") (class "Default")
      (node (ref "ARDUINO") (pin "D11") (pinfunction "D11_D11") (pintype "bidirectional"))
      (node (ref "U$13") (pin "P$5") (pinfunction "5_P$5") (pintype "bidirectional"))
    )
    (net (code "54") (name "Net-(U$13-6)") (class "Default")
      (node (ref "ARDUINO") (pin "D10") (pinfunction "D10_D10") (pintype "bidirectional"))
      (node (ref "U$13") (pin "P$6") (pinfunction "6_P$6") (pintype "bidirectional"))
    )
    (net (code "55") (name "Net-(U$13-7)") (class "Default")
      (node (ref "ARDUINO") (pin "D9") (pinfunction "D9_D9") (pintype "bidirectional"))
      (node (ref "U$13") (pin "P$7") (pinfunction "7_P$7") (pintype "bidirectional"))
    )
    (net (code "56") (name "Net-(U$13-8)") (class "Default")
      (node (ref "ARDUINO") (pin "D8") (pinfunction "D8_D8") (pintype "bidirectional"))
      (node (ref "U$13") (pin "P$8") (pinfunction "8_P$8") (pintype "bidirectional"))
    )
    (net (code "57") (name "unconnected-(Q1-X1-Pad1)") (class "Default")
      (node (ref "Q1") (pin "1") (pinfunction "X1_1") (pintype "bidirectional"))
    )
    (net (code "58") (name "unconnected-(Q1-X2-Pad3)") (class "Default")
      (node (ref "Q1") (pin "3") (pinfunction "X2_3") (pintype "bidirectional"))
    )
    (net (code "59") (name "unconnected-(S1-P1-Pad2)") (class "Default")
      (node (ref "S1") (pin "2") (pinfunction "P1_2") (pintype "passive"))
    )
    (net (code "60") (name "unconnected-(S1-S1-Pad4)") (class "Default")
      (node (ref "S1") (pin "4") (pinfunction "S1_4") (pintype "passive"))
    )
    (net (code "61") (name "unconnected-(SAM2695-VCMHPOUT-Pad3)") (class "Default")
      (node (ref "SAM2695") (pin "3") (pinfunction "VCMHPOUT_3") (pintype "output"))
    )
  )
)
